# piezo-preamp-tickler_V3-1_dual-supply-TL.net
KiCad netlist of a schematic drawn in EAGLE
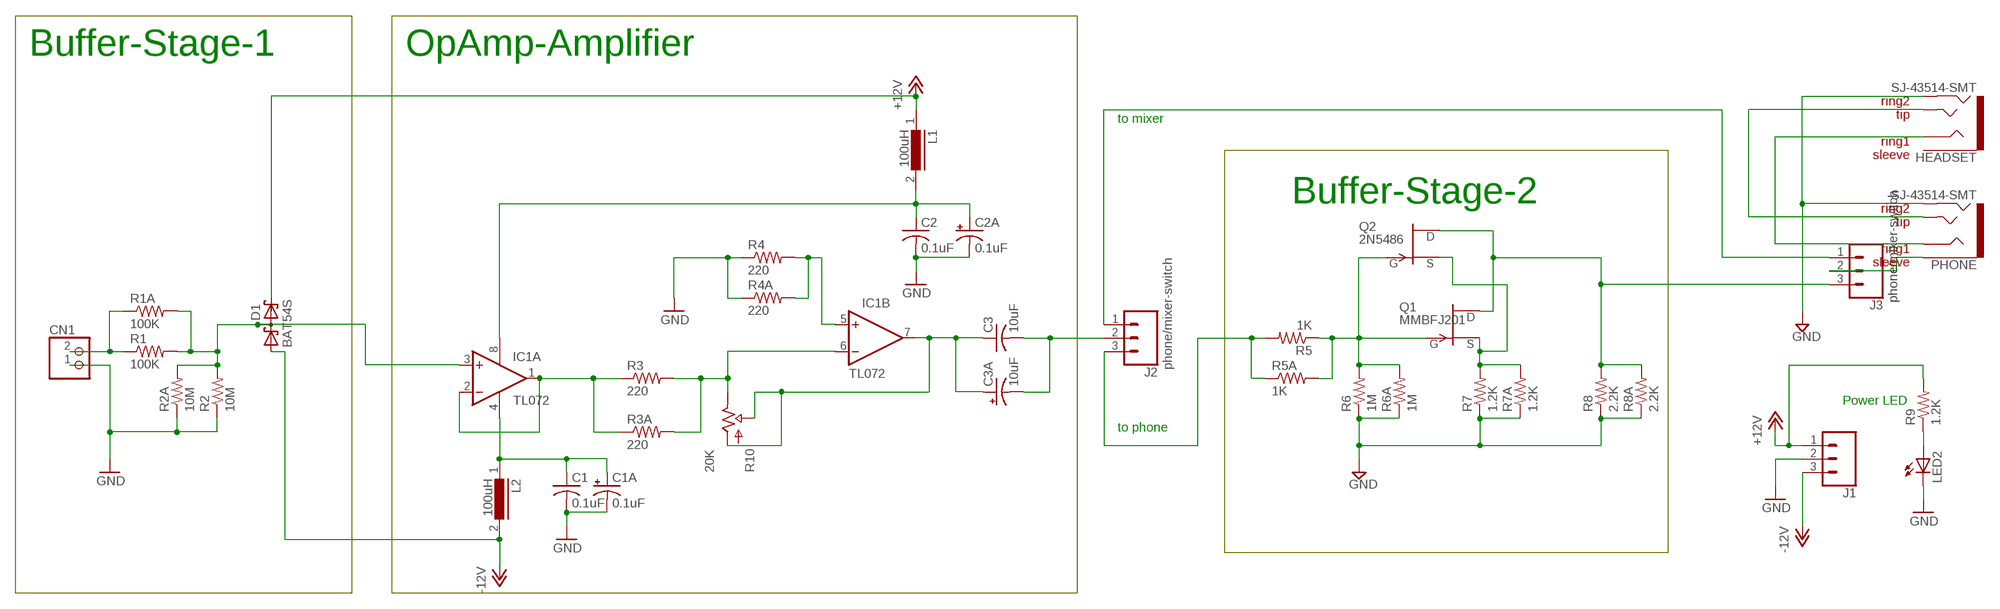
[diagram p0: schematic, sheet 1]

(export (version "E")
  (design (tool "Eeschema 10.0.6"))
  (components
    (comp (ref "C1")
      (value "0.1uF")
      (footprint "eagle-import:C0805K")
      (libsource (lib "eagle-import") (part "C-USC0805K"))
    )
    (comp (ref "C1A")
      (value "0.1uF")
      (footprint "eagle-import:E2,5-6E")
      (libsource (lib "eagle-import") (part "CPOL-USE2,5-6E"))
    )
    (comp (ref "C2")
      (value "0.1uF")
      (footprint "eagle-import:C0805K")
      (libsource (lib "eagle-import") (part "C-USC0805K"))
    )
    (comp (ref "C2A")
      (value "0.1uF")
      (footprint "eagle-import:E2,5-6E")
      (libsource (lib "eagle-import") (part "CPOL-USE2,5-6E"))
    )
    (comp (ref "C3")
      (value "10uF")
      (footprint "eagle-import:C1206")
      (libsource (lib "eagle-import") (part "C-USC1206"))
    )
    (comp (ref "C3A")
      (value "10uF")
      (footprint "eagle-import:E2,5-6E")
      (libsource (lib "eagle-import") (part "CPOL-USE2,5-6E"))
    )
    (comp (ref "CN1")
      (value "JST_2PIN-THM")
      (footprint "eagle-import:JST-PH-2-THM")
      (libsource (lib "eagle-import") (part "JST_2PIN-THM"))
    )
    (comp (ref "D1")
      (value "BAT54S")
      (footprint "eagle-import:SOT23")
      (libsource (lib "eagle-import") (part "BAT54S"))
    )
    (comp (ref "HEADSET")
      (value "SJ-43514-SMT")
      (footprint "eagle-import:TRRS_SJ-43514-SMT-TR")
      (libsource (lib "eagle-import") (part "TRRS-3.5MMLGPADS"))
    )
    (comp (ref "IC1")
      (value "TL072")
      (footprint "eagle-import:SO08")
      (libsource (lib "eagle-import") (part "OPA2UA134"))
    )
    (comp (ref "J1")
      (value "CONN_03LOCK")
      (footprint "eagle-import:1X03_LOCK")
      (libsource (lib "eagle-import") (part "CONN_03LOCK"))
    )
    (comp (ref "J2")
      (value "phone/mixer-switch")
      (footprint "eagle-import:1X03_LOCK")
      (libsource (lib "eagle-import") (part "CONN_03LOCK"))
    )
    (comp (ref "J3")
      (value "phone/mixer-switch")
      (footprint "eagle-import:1X03_LOCK")
      (libsource (lib "eagle-import") (part "CONN_03LOCK"))
    )
    (comp (ref "L1")
      (value "100uH")
      (footprint "eagle-import:LBC-SE")
      (libsource (lib "eagle-import") (part "LBC-SE"))
    )
    (comp (ref "L2")
      (value "100uH")
      (footprint "eagle-import:LBC-SE")
      (libsource (lib "eagle-import") (part "LBC-SE"))
    )
    (comp (ref "LED2")
      (value "LED3MM")
      (footprint "eagle-import:LED3MM")
      (libsource (lib "eagle-import") (part "LED3MM"))
    )
    (comp (ref "PHONE")
      (value "SJ-43514-SMT")
      (footprint "eagle-import:TRRS_SJ-43514-SMT-TR")
      (libsource (lib "eagle-import") (part "TRRS-3.5MMLGPADS"))
    )
    (comp (ref "Q1")
      (value "MMBFJ201")
      (footprint "eagle-import:SOT23")
      (libsource (lib "eagle-import") (part "transistor-fet_396_?548SST4"))
    )
    (comp (ref "Q2")
      (value "2N5486")
      (footprint "eagle-import:TO92-")
      (libsource (lib "eagle-import") (part "?5482N6"))
    )
    (comp (ref "R1")
      (value "100K")
      (footprint "eagle-import:R0603")
      (libsource (lib "eagle-import") (part "R-US_R0603"))
    )
    (comp (ref "R1A")
      (value "100K")
      (footprint "eagle-import:0204V")
      (libsource (lib "eagle-import") (part "R-US_0204/2V"))
    )
    (comp (ref "R2")
      (value "10M")
      (footprint "eagle-import:R0603")
      (libsource (lib "eagle-import") (part "R-US_R0603"))
    )
    (comp (ref "R2A")
      (value "10M")
      (footprint "eagle-import:0204V")
      (libsource (lib "eagle-import") (part "R-US_0204/2V"))
    )
    (comp (ref "R3")
      (value "220")
      (footprint "eagle-import:R0603")
      (libsource (lib "eagle-import") (part "R-US_R0603"))
    )
    (comp (ref "R3A")
      (value "220")
      (footprint "eagle-import:0204V")
      (libsource (lib "eagle-import") (part "R-US_0204/2V"))
    )
    (comp (ref "R4")
      (value "220")
      (footprint "eagle-import:R0603")
      (libsource (lib "eagle-import") (part "R-US_R0603"))
    )
    (comp (ref "R4A")
      (value "220")
      (footprint "eagle-import:0204V")
      (libsource (lib "eagle-import") (part "R-US_0204/2V"))
    )
    (comp (ref "R5")
      (value "1K")
      (footprint "eagle-import:R0603")
      (libsource (lib "eagle-import") (part "R-US_R0603"))
    )
    (comp (ref "R5A")
      (value "1K")
      (footprint "eagle-import:0204V")
      (libsource (lib "eagle-import") (part "R-US_0204/2V"))
    )
    (comp (ref "R6")
      (value "1M")
      (footprint "eagle-import:R0603")
      (libsource (lib "eagle-import") (part "R-US_R0603"))
    )
    (comp (ref "R6A")
      (value "1M")
      (footprint "eagle-import:0204V")
      (libsource (lib "eagle-import") (part "R-US_0204/2V"))
    )
    (comp (ref "R7")
      (value "1.2K")
      (footprint "eagle-import:R0603")
      (libsource (lib "eagle-import") (part "R-US_R0603"))
    )
    (comp (ref "R7A")
      (value "1.2K")
      (footprint "eagle-import:0204V")
      (libsource (lib "eagle-import") (part "R-US_0204/2V"))
    )
    (comp (ref "R8")
      (value "2.2K")
      (footprint "eagle-import:R0603")
      (libsource (lib "eagle-import") (part "R-US_R0603"))
    )
    (comp (ref "R8A")
      (value "2.2K")
      (footprint "eagle-import:0204V")
      (libsource (lib "eagle-import") (part "R-US_0204/2V"))
    )
    (comp (ref "R9")
      (value "1.2K")
      (footprint "eagle-import:0204V")
      (libsource (lib "eagle-import") (part "R-US_0204/2V"))
    )
    (comp (ref "R10")
      (value "20K")
      (footprint "eagle-import:TRIMPOT-MULTI")
      (libsource (lib "eagle-import") (part "POTTRIMPOT-MULTI"))
    )
  )
  (nets
    (net (code "1") (name "+12V") (class "Default")
      (node (ref "D1") (pin "2") (pinfunction "C2_2") (pintype "passive"))
      (node (ref "J1") (pin "1") (pinfunction "1_1") (pintype "passive"))
      (node (ref "L1") (pin "1") (pinfunction "1_1") (pintype "passive"))
      (node (ref "R9") (pin "2") (pinfunction "2_2") (pintype "passive"))
    )
    (net (code "2") (name "-12V") (class "Default")
      (node (ref "D1") (pin "1") (pinfunction "A1_1") (pintype "passive"))
      (node (ref "J1") (pin "3") (pinfunction "3_3") (pintype "passive"))
      (node (ref "L2") (pin "2") (pinfunction "2_2") (pintype "passive"))
    )
    (net (code "3") (name "GND") (class "Default")
      (node (ref "C1") (pin "2") (pinfunction "2_2") (pintype "passive"))
      (node (ref "C1A") (pin "-") (pinfunction "-_-") (pintype "passive"))
      (node (ref "C2") (pin "2") (pinfunction "2_2") (pintype "passive"))
      (node (ref "C2A") (pin "-") (pinfunction "-_-") (pintype "passive"))
      (node (ref "CN1") (pin "1") (pinfunction "2_1") (pintype "passive"))
      (node (ref "HEADSET") (pin "RING2") (pinfunction "RING2_RING2") (pintype "bidirectional"))
      (node (ref "J1") (pin "2") (pinfunction "2_2") (pintype "passive"))
      (node (ref "LED2") (pin "K") (pinfunction "C_K") (pintype "passive"))
      (node (ref "PHONE") (pin "RING2") (pinfunction "RING2_RING2") (pintype "bidirectional"))
      (node (ref "R2") (pin "1") (pinfunction "1_1") (pintype "passive"))
      (node (ref "R2A") (pin "1") (pinfunction "1_1") (pintype "passive"))
      (node (ref "R4") (pin "1") (pinfunction "1_1") (pintype "passive"))
      (node (ref "R4A") (pin "1") (pinfunction "1_1") (pintype "passive"))
      (node (ref "R6") (pin "1") (pinfunction "1_1") (pintype "passive"))
      (node (ref "R6A") (pin "1") (pinfunction "1_1") (pintype "passive"))
      (node (ref "R7") (pin "1") (pinfunction "1_1") (pintype "passive"))
      (node (ref "R7A") (pin "1") (pinfunction "1_1") (pintype "passive"))
      (node (ref "R8") (pin "1") (pinfunction "1_1") (pintype "passive"))
      (node (ref "R8A") (pin "1") (pinfunction "1_1") (pintype "passive"))
    )
    (net (code "4") (name "Net-(C3-Pad2)") (class "Default")
      (node (ref "C3") (pin "2") (pinfunction "2_2") (pintype "passive"))
      (node (ref "C3A") (pin "-") (pinfunction "-_-") (pintype "passive"))
      (node (ref "J2") (pin "2") (pinfunction "2_2") (pintype "passive"))
    )
    (net (code "5") (name "Net-(CN1-1)") (class "Default")
      (node (ref "CN1") (pin "2") (pinfunction "1_2") (pintype "passive"))
      (node (ref "R1") (pin "1") (pinfunction "1_1") (pintype "passive"))
      (node (ref "R1A") (pin "1") (pinfunction "1_1") (pintype "passive"))
    )
    (net (code "6") (name "Net-(D1-C1A2)") (class "Default")
      (node (ref "D1") (pin "3") (pinfunction "C1A2_3") (pintype "passive"))
      (node (ref "IC1") (pin "3") (pinfunction "+IN_3") (pintype "input"))
      (node (ref "R1") (pin "2") (pinfunction "2_2") (pintype "passive"))
      (node (ref "R1A") (pin "2") (pinfunction "2_2") (pintype "passive"))
      (node (ref "R2") (pin "2") (pinfunction "2_2") (pintype "passive"))
      (node (ref "R2A") (pin "2") (pinfunction "2_2") (pintype "passive"))
    )
    (net (code "7") (name "Net-(HEADSET-PadRING1)") (class "Default")
      (node (ref "HEADSET") (pin "RING1") (pinfunction "RING1_RING1") (pintype "bidirectional"))
      (node (ref "PHONE") (pin "RING1") (pinfunction "RING1_RING1") (pintype "bidirectional"))
    )
    (net (code "8") (name "Net-(HEADSET-PadTIP)") (class "Default")
      (node (ref "HEADSET") (pin "TIP") (pinfunction "TIP_TIP") (pintype "bidirectional"))
      (node (ref "PHONE") (pin "TIP") (pinfunction "TIP_TIP") (pintype "bidirectional"))
    )
    (net (code "9") (name "Net-(IC1A--IN)") (class "Default")
      (node (ref "IC1") (pin "1") (pinfunction "OUT_1") (pintype "output"))
      (node (ref "IC1") (pin "2") (pinfunction "-IN_2") (pintype "input"))
      (node (ref "R3") (pin "1") (pinfunction "1_1") (pintype "passive"))
      (node (ref "R3A") (pin "1") (pinfunction "1_1") (pintype "passive"))
    )
    (net (code "10") (name "Net-(IC1A-V+)") (class "Default")
      (node (ref "C2") (pin "1") (pinfunction "1_1") (pintype "passive"))
      (node (ref "C2A") (pin "+") (pinfunction "+_+") (pintype "passive"))
      (node (ref "IC1") (pin "8") (pinfunction "V+_8") (pintype "power_in"))
      (node (ref "L1") (pin "2") (pinfunction "2_2") (pintype "passive"))
    )
    (net (code "11") (name "Net-(IC1A-V-)") (class "Default")
      (node (ref "C1") (pin "1") (pinfunction "1_1") (pintype "passive"))
      (node (ref "C1A") (pin "+") (pinfunction "+_+") (pintype "passive"))
      (node (ref "IC1") (pin "4") (pinfunction "V-_4") (pintype "power_in"))
      (node (ref "L2") (pin "1") (pinfunction "1_1") (pintype "passive"))
    )
    (net (code "12") (name "Net-(IC1B-+IN)") (class "Default")
      (node (ref "IC1") (pin "5") (pinfunction "+IN_5") (pintype "input"))
      (node (ref "R4") (pin "2") (pinfunction "2_2") (pintype "passive"))
      (node (ref "R4A") (pin "2") (pinfunction "2_2") (pintype "passive"))
    )
    (net (code "13") (name "Net-(IC1B--IN)") (class "Default")
      (node (ref "IC1") (pin "6") (pinfunction "-IN_6") (pintype "input"))
      (node (ref "R10") (pin "P$1") (pinfunction "OUT_P$1") (pintype "passive"))
      (node (ref "R10") (pin "P$3") (pinfunction "OUT_P$3") (pintype "passive"))
      (node (ref "R10") (pin "P$4") (pinfunction "OUT_P$4") (pintype "passive"))
      (node (ref "R10") (pin "P$6") (pinfunction "OUT_P$6") (pintype "passive"))
      (node (ref "R10") (pin "P$9") (pinfunction "OUT_P$9") (pintype "passive"))
      (node (ref "R3") (pin "2") (pinfunction "2_2") (pintype "passive"))
      (node (ref "R3A") (pin "2") (pinfunction "2_2") (pintype "passive"))
    )
    (net (code "14") (name "Net-(IC1B-OUT)") (class "Default")
      (node (ref "C3") (pin "1") (pinfunction "1_1") (pintype "passive"))
      (node (ref "C3A") (pin "+") (pinfunction "+_+") (pintype "passive"))
      (node (ref "IC1") (pin "7") (pinfunction "OUT_7") (pintype "output"))
      (node (ref "R10") (pin "P$10") (pinfunction "WIPER_P$10") (pintype "passive"))
      (node (ref "R10") (pin "P$12") (pinfunction "WIPER_P$12") (pintype "passive"))
      (node (ref "R10") (pin "P$13") (pinfunction "WIPER_P$13") (pintype "passive"))
      (node (ref "R10") (pin "P$15") (pinfunction "WIPER_P$15") (pintype "passive"))
      (node (ref "R10") (pin "P$16") (pinfunction "WIPER_P$16") (pintype "passive"))
      (node (ref "R10") (pin "P$18") (pinfunction "WIPER_P$18") (pintype "passive"))
      (node (ref "R10") (pin "P$20") (pinfunction "IN_P$20") (pintype "passive"))
      (node (ref "R10") (pin "P$21") (pinfunction "IN_P$21") (pintype "passive"))
      (node (ref "R10") (pin "P$22") (pinfunction "IN_P$22") (pintype "passive"))
      (node (ref "R10") (pin "P$24") (pinfunction "IN_P$24") (pintype "passive"))
      (node (ref "R10") (pin "P$27") (pinfunction "IN_P$27") (pintype "passive"))
    )
    (net (code "15") (name "Net-(J2-Pad1)") (class "Default")
      (node (ref "J2") (pin "1") (pinfunction "1_1") (pintype "passive"))
      (node (ref "J3") (pin "1") (pinfunction "1_1") (pintype "passive"))
    )
    (net (code "16") (name "Net-(J2-Pad3)") (class "Default")
      (node (ref "J2") (pin "3") (pinfunction "3_3") (pintype "passive"))
      (node (ref "R5") (pin "2") (pinfunction "2_2") (pintype "passive"))
      (node (ref "R5A") (pin "1") (pinfunction "1_1") (pintype "passive"))
    )
    (net (code "17") (name "Net-(J3-Pad2)") (class "Default")
      (node (ref "J3") (pin "2") (pinfunction "2_2") (pintype "passive"))
      (node (ref "PHONE") (pin "EARTH") (pinfunction "EARTH_EARTH") (pintype "bidirectional"))
    )
    (net (code "18") (name "Net-(LED2-PadA)") (class "Default")
      (node (ref "LED2") (pin "A") (pinfunction "A_A") (pintype "passive"))
      (node (ref "R9") (pin "1") (pinfunction "1_1") (pintype "passive"))
    )
    (net (code "19") (name "Net-(Q1-D)") (class "Default")
      (node (ref "J3") (pin "3") (pinfunction "3_3") (pintype "passive"))
      (node (ref "Q1") (pin "1") (pinfunction "D_1") (pintype "passive"))
      (node (ref "Q2") (pin "3") (pinfunction "D_3") (pintype "passive"))
      (node (ref "R8") (pin "2") (pinfunction "2_2") (pintype "passive"))
      (node (ref "R8A") (pin "2") (pinfunction "2_2") (pintype "passive"))
    )
    (net (code "20") (name "Net-(Q1-G)") (class "Default")
      (node (ref "Q1") (pin "3") (pinfunction "G_3") (pintype "passive"))
      (node (ref "Q2") (pin "1") (pinfunction "G_1") (pintype "passive"))
      (node (ref "R5") (pin "1") (pinfunction "1_1") (pintype "passive"))
      (node (ref "R5A") (pin "2") (pinfunction "2_2") (pintype "passive"))
      (node (ref "R6") (pin "2") (pinfunction "2_2") (pintype "passive"))
      (node (ref "R6A") (pin "2") (pinfunction "2_2") (pintype "passive"))
    )
    (net (code "21") (name "Net-(Q1-S)") (class "Default")
      (node (ref "Q1") (pin "2") (pinfunction "S_2") (pintype "passive"))
      (node (ref "Q2") (pin "2") (pinfunction "S_2") (pintype "passive"))
      (node (ref "R7") (pin "2") (pinfunction "2_2") (pintype "passive"))
      (node (ref "R7A") (pin "2") (pinfunction "2_2") (pintype "passive"))
    )
    (net (code "22") (name "unconnected-(HEADSET-PadEARTH)") (class "Default")
      (node (ref "HEADSET") (pin "EARTH") (pinfunction "EARTH_EARTH") (pintype "bidirectional"))
    )
  )
)
